# motor_driver.net
KiCad netlist of a schematic drawn in EAGLE
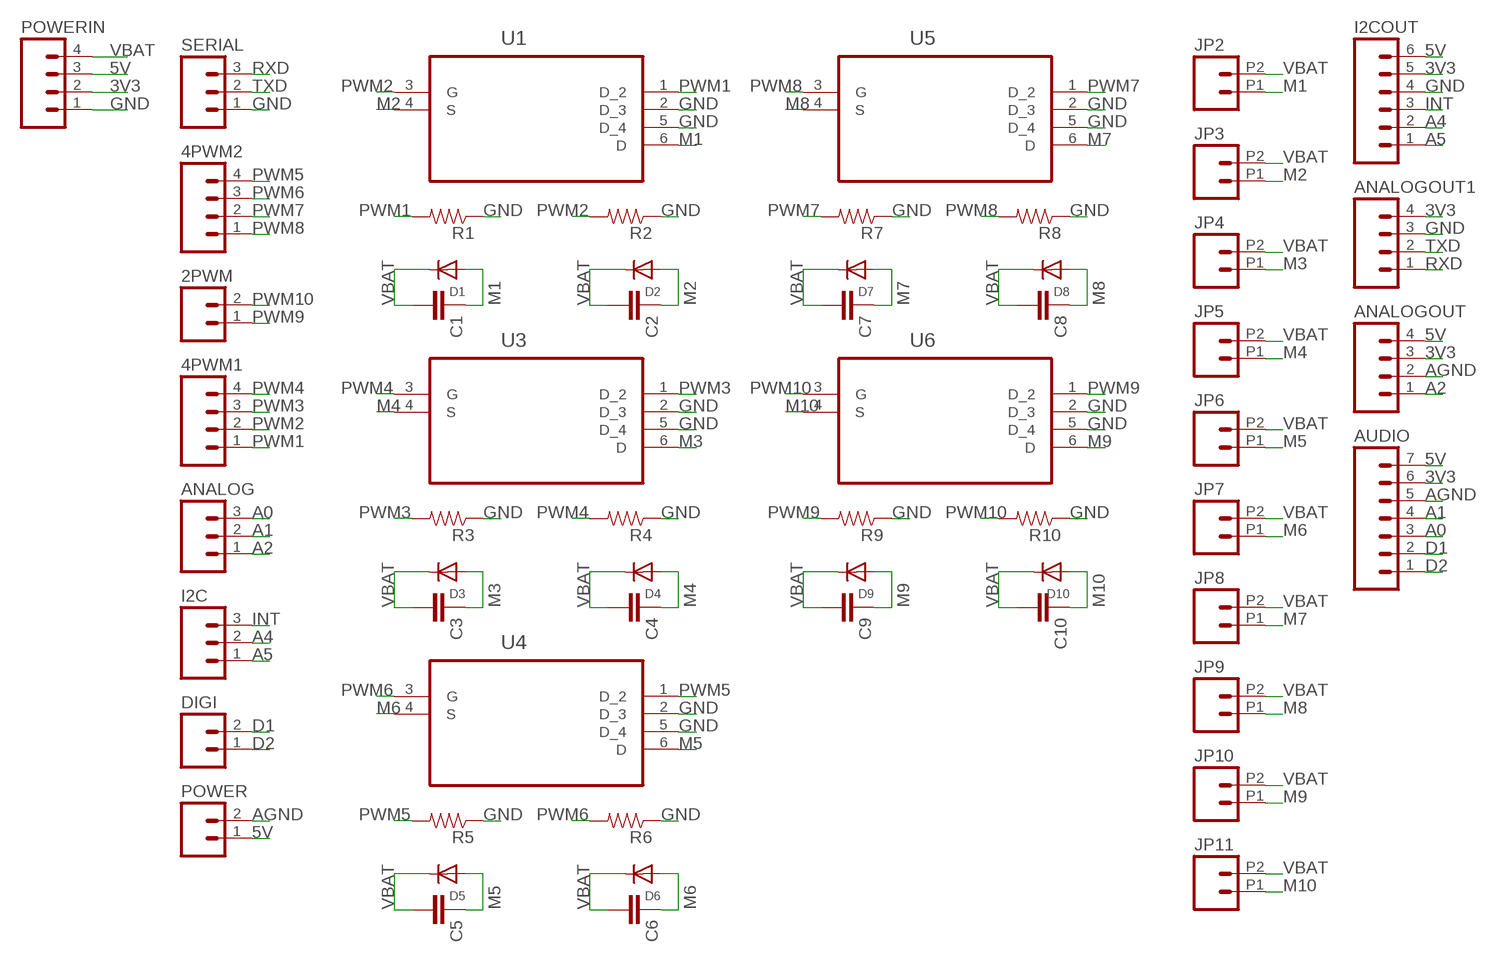
[diagram p0: schematic, sheet 1]

(export (version "E")
  (design (tool "Eeschema 10.0.6"))
  (components
    (comp (ref "2PWM")
      (value "M02PTH")
      (footprint "eagle-import:1X02")
      (libsource (lib "eagle-import") (part "M02PTH"))
    )
    (comp (ref "4PWM1")
      (value "M04PTH")
      (footprint "eagle-import:1X04")
      (libsource (lib "eagle-import") (part "M04PTH"))
    )
    (comp (ref "4PWM2")
      (value "M04PTH")
      (footprint "eagle-import:1X04")
      (libsource (lib "eagle-import") (part "M04PTH"))
    )
    (comp (ref "ANALOG")
      (value "M03PTH")
      (footprint "eagle-import:1X03")
      (libsource (lib "eagle-import") (part "M03PTH"))
    )
    (comp (ref "ANALOGOUT")
      (value "M04PTH")
      (footprint "eagle-import:1X04")
      (libsource (lib "eagle-import") (part "M04PTH"))
    )
    (comp (ref "ANALOGOUT1")
      (value "M04PTH")
      (footprint "eagle-import:1X04")
      (libsource (lib "eagle-import") (part "M04PTH"))
    )
    (comp (ref "AUDIO")
      (value "M07")
      (footprint "eagle-import:1X07")
      (libsource (lib "eagle-import") (part "M07"))
    )
    (comp (ref "C1")
      (value "CAP0603-CAP")
      (footprint "eagle-import:0603-CAP")
      (libsource (lib "eagle-import") (part "CAP0603-CAP"))
    )
    (comp (ref "C2")
      (value "CAP0603-CAP")
      (footprint "eagle-import:0603-CAP")
      (libsource (lib "eagle-import") (part "CAP0603-CAP"))
    )
    (comp (ref "C3")
      (value "CAP0603-CAP")
      (footprint "eagle-import:0603-CAP")
      (libsource (lib "eagle-import") (part "CAP0603-CAP"))
    )
    (comp (ref "C4")
      (value "CAP0603-CAP")
      (footprint "eagle-import:0603-CAP")
      (libsource (lib "eagle-import") (part "CAP0603-CAP"))
    )
    (comp (ref "C5")
      (value "CAP0603-CAP")
      (footprint "eagle-import:0603-CAP")
      (libsource (lib "eagle-import") (part "CAP0603-CAP"))
    )
    (comp (ref "C6")
      (value "CAP0603-CAP")
      (footprint "eagle-import:0603-CAP")
      (libsource (lib "eagle-import") (part "CAP0603-CAP"))
    )
    (comp (ref "C7")
      (value "CAP0603-CAP")
      (footprint "eagle-import:0603-CAP")
      (libsource (lib "eagle-import") (part "CAP0603-CAP"))
    )
    (comp (ref "C8")
      (value "CAP0603-CAP")
      (footprint "eagle-import:0603-CAP")
      (libsource (lib "eagle-import") (part "CAP0603-CAP"))
    )
    (comp (ref "C9")
      (value "CAP0603-CAP")
      (footprint "eagle-import:0603-CAP")
      (libsource (lib "eagle-import") (part "CAP0603-CAP"))
    )
    (comp (ref "C10")
      (value "CAP0603-CAP")
      (footprint "eagle-import:0603-CAP")
      (libsource (lib "eagle-import") (part "CAP0603-CAP"))
    )
    (comp (ref "D1")
      (value "DIODE_SOD-123FL")
      (footprint "eagle-import:SOD-123FL")
      (libsource (lib "eagle-import") (part "DIODE_SOD-123FL"))
    )
    (comp (ref "D2")
      (value "DIODE_SOD-123FL")
      (footprint "eagle-import:SOD-123FL")
      (libsource (lib "eagle-import") (part "DIODE_SOD-123FL"))
    )
    (comp (ref "D3")
      (value "DIODE_SOD-123FL")
      (footprint "eagle-import:SOD-123FL")
      (libsource (lib "eagle-import") (part "DIODE_SOD-123FL"))
    )
    (comp (ref "D4")
      (value "DIODE_SOD-123FL")
      (footprint "eagle-import:SOD-123FL")
      (libsource (lib "eagle-import") (part "DIODE_SOD-123FL"))
    )
    (comp (ref "D5")
      (value "DIODE_SOD-123FL")
      (footprint "eagle-import:SOD-123FL")
      (libsource (lib "eagle-import") (part "DIODE_SOD-123FL"))
    )
    (comp (ref "D6")
      (value "DIODE_SOD-123FL")
      (footprint "eagle-import:SOD-123FL")
      (libsource (lib "eagle-import") (part "DIODE_SOD-123FL"))
    )
    (comp (ref "D7")
      (value "DIODE_SOD-123FL")
      (footprint "eagle-import:SOD-123FL")
      (libsource (lib "eagle-import") (part "DIODE_SOD-123FL"))
    )
    (comp (ref "D8")
      (value "DIODE_SOD-123FL")
      (footprint "eagle-import:SOD-123FL")
      (libsource (lib "eagle-import") (part "DIODE_SOD-123FL"))
    )
    (comp (ref "D9")
      (value "DIODE_SOD-123FL")
      (footprint "eagle-import:SOD-123FL")
      (libsource (lib "eagle-import") (part "DIODE_SOD-123FL"))
    )
    (comp (ref "D10")
      (value "DIODE_SOD-123FL")
      (footprint "eagle-import:SOD-123FL")
      (libsource (lib "eagle-import") (part "DIODE_SOD-123FL"))
    )
    (comp (ref "DIGI")
      (value "M02PTH")
      (footprint "eagle-import:1X02")
      (libsource (lib "eagle-import") (part "M02PTH"))
    )
    (comp (ref "I2C")
      (value "M03PTH")
      (footprint "eagle-import:1X03")
      (libsource (lib "eagle-import") (part "M03PTH"))
    )
    (comp (ref "I2COUT")
      (value "M06NO_SILK")
      (footprint "eagle-import:1X06_NO_SILK")
      (libsource (lib "eagle-import") (part "M06NO_SILK"))
    )
    (comp (ref "JP2")
      (value "M022.54MM_SCREWTERM")
      (footprint "eagle-import:1X02_2.54_SCREWTERM")
      (libsource (lib "eagle-import") (part "M022.54MM_SCREWTERM"))
    )
    (comp (ref "JP3")
      (value "M022.54MM_SCREWTERM")
      (footprint "eagle-import:1X02_2.54_SCREWTERM")
      (libsource (lib "eagle-import") (part "M022.54MM_SCREWTERM"))
    )
    (comp (ref "JP4")
      (value "M022.54MM_SCREWTERM")
      (footprint "eagle-import:1X02_2.54_SCREWTERM")
      (libsource (lib "eagle-import") (part "M022.54MM_SCREWTERM"))
    )
    (comp (ref "JP5")
      (value "M022.54MM_SCREWTERM")
      (footprint "eagle-import:1X02_2.54_SCREWTERM")
      (libsource (lib "eagle-import") (part "M022.54MM_SCREWTERM"))
    )
    (comp (ref "JP6")
      (value "M022.54MM_SCREWTERM")
      (footprint "eagle-import:1X02_2.54_SCREWTERM")
      (libsource (lib "eagle-import") (part "M022.54MM_SCREWTERM"))
    )
    (comp (ref "JP7")
      (value "M022.54MM_SCREWTERM")
      (footprint "eagle-import:1X02_2.54_SCREWTERM")
      (libsource (lib "eagle-import") (part "M022.54MM_SCREWTERM"))
    )
    (comp (ref "JP8")
      (value "M022.54MM_SCREWTERM")
      (footprint "eagle-import:1X02_2.54_SCREWTERM")
      (libsource (lib "eagle-import") (part "M022.54MM_SCREWTERM"))
    )
    (comp (ref "JP9")
      (value "M022.54MM_SCREWTERM")
      (footprint "eagle-import:1X02_2.54_SCREWTERM")
      (libsource (lib "eagle-import") (part "M022.54MM_SCREWTERM"))
    )
    (comp (ref "JP10")
      (value "M022.54MM_SCREWTERM")
      (footprint "eagle-import:1X02_2.54_SCREWTERM")
      (libsource (lib "eagle-import") (part "M022.54MM_SCREWTERM"))
    )
    (comp (ref "JP11")
      (value "M022.54MM_SCREWTERM")
      (footprint "eagle-import:1X02_2.54_SCREWTERM")
      (libsource (lib "eagle-import") (part "M022.54MM_SCREWTERM"))
    )
    (comp (ref "POWER")
      (value "M02PTH")
      (footprint "eagle-import:1X02")
      (libsource (lib "eagle-import") (part "M02PTH"))
    )
    (comp (ref "POWERIN")
      (value "M04PTH")
      (footprint "eagle-import:1X04")
      (libsource (lib "eagle-import") (part "M04PTH"))
    )
    (comp (ref "R1")
      (value "RESISTOR0603")
      (footprint "eagle-import:0603-RES")
      (libsource (lib "eagle-import") (part "RESISTOR0603"))
    )
    (comp (ref "R2")
      (value "RESISTOR0603")
      (footprint "eagle-import:0603-RES")
      (libsource (lib "eagle-import") (part "RESISTOR0603"))
    )
    (comp (ref "R3")
      (value "RESISTOR0603")
      (footprint "eagle-import:0603-RES")
      (libsource (lib "eagle-import") (part "RESISTOR0603"))
    )
    (comp (ref "R4")
      (value "RESISTOR0603")
      (footprint "eagle-import:0603-RES")
      (libsource (lib "eagle-import") (part "RESISTOR0603"))
    )
    (comp (ref "R5")
      (value "RESISTOR0603")
      (footprint "eagle-import:0603-RES")
      (libsource (lib "eagle-import") (part "RESISTOR0603"))
    )
    (comp (ref "R6")
      (value "RESISTOR0603")
      (footprint "eagle-import:0603-RES")
      (libsource (lib "eagle-import") (part "RESISTOR0603"))
    )
    (comp (ref "R7")
      (value "RESISTOR0603")
      (footprint "eagle-import:0603-RES")
      (libsource (lib "eagle-import") (part "RESISTOR0603"))
    )
    (comp (ref "R8")
      (value "RESISTOR0603")
      (footprint "eagle-import:0603-RES")
      (libsource (lib "eagle-import") (part "RESISTOR0603"))
    )
    (comp (ref "R9")
      (value "RESISTOR0603")
      (footprint "eagle-import:0603-RES")
      (libsource (lib "eagle-import") (part "RESISTOR0603"))
    )
    (comp (ref "R10")
      (value "RESISTOR0603")
      (footprint "eagle-import:0603-RES")
      (libsource (lib "eagle-import") (part "RESISTOR0603"))
    )
    (comp (ref "SERIAL")
      (value "M03PTH")
      (footprint "eagle-import:1X03")
      (libsource (lib "eagle-import") (part "M03PTH"))
    )
    (comp (ref "U1")
      (value "SI3456DDV-T1-GE3")
      (footprint "eagle-import:SOT95P285X110-6N")
      (libsource (lib "eagle-import") (part "SI3456DDV-T1-GE3"))
    )
    (comp (ref "U3")
      (value "SI3456DDV-T1-GE3")
      (footprint "eagle-import:SOT95P285X110-6N")
      (libsource (lib "eagle-import") (part "SI3456DDV-T1-GE3"))
    )
    (comp (ref "U4")
      (value "SI3456DDV-T1-GE3")
      (footprint "eagle-import:SOT95P285X110-6N")
      (libsource (lib "eagle-import") (part "SI3456DDV-T1-GE3"))
    )
    (comp (ref "U5")
      (value "SI3456DDV-T1-GE3")
      (footprint "eagle-import:SOT95P285X110-6N")
      (libsource (lib "eagle-import") (part "SI3456DDV-T1-GE3"))
    )
    (comp (ref "U6")
      (value "SI3456DDV-T1-GE3")
      (footprint "eagle-import:SOT95P285X110-6N")
      (libsource (lib "eagle-import") (part "SI3456DDV-T1-GE3"))
    )
  )
  (nets
    (net (code "1") (name "/3V3") (class "Default")
      (node (ref "ANALOGOUT") (pin "3") (pinfunction "3_3") (pintype "passive"))
      (node (ref "ANALOGOUT1") (pin "4") (pinfunction "4_4") (pintype "passive"))
      (node (ref "AUDIO") (pin "6") (pinfunction "6_6") (pintype "passive"))
      (node (ref "I2COUT") (pin "5") (pinfunction "5_5") (pintype "passive"))
      (node (ref "POWERIN") (pin "2") (pinfunction "2_2") (pintype "passive"))
    )
    (net (code "2") (name "/5V") (class "Default")
      (node (ref "ANALOGOUT") (pin "4") (pinfunction "4_4") (pintype "passive"))
      (node (ref "AUDIO") (pin "7") (pinfunction "7_7") (pintype "passive"))
      (node (ref "I2COUT") (pin "6") (pinfunction "6_6") (pintype "passive"))
      (node (ref "POWER") (pin "1") (pinfunction "1_1") (pintype "passive"))
      (node (ref "POWERIN") (pin "3") (pinfunction "3_3") (pintype "passive"))
    )
    (net (code "3") (name "/A0") (class "Default")
      (node (ref "ANALOG") (pin "3") (pinfunction "3_3") (pintype "passive"))
      (node (ref "AUDIO") (pin "3") (pinfunction "3_3") (pintype "passive"))
    )
    (net (code "4") (name "/A1") (class "Default")
      (node (ref "ANALOG") (pin "2") (pinfunction "2_2") (pintype "passive"))
      (node (ref "AUDIO") (pin "4") (pinfunction "4_4") (pintype "passive"))
    )
    (net (code "5") (name "/A2") (class "Default")
      (node (ref "ANALOG") (pin "1") (pinfunction "1_1") (pintype "passive"))
      (node (ref "ANALOGOUT") (pin "1") (pinfunction "1_1") (pintype "passive"))
    )
    (net (code "6") (name "/A4") (class "Default")
      (node (ref "I2C") (pin "2") (pinfunction "2_2") (pintype "passive"))
      (node (ref "I2COUT") (pin "2") (pinfunction "2_2") (pintype "passive"))
    )
    (net (code "7") (name "/A5") (class "Default")
      (node (ref "I2C") (pin "1") (pinfunction "1_1") (pintype "passive"))
      (node (ref "I2COUT") (pin "1") (pinfunction "1_1") (pintype "passive"))
    )
    (net (code "8") (name "/AGND") (class "Default")
      (node (ref "ANALOGOUT") (pin "2") (pinfunction "2_2") (pintype "passive"))
      (node (ref "AUDIO") (pin "5") (pinfunction "5_5") (pintype "passive"))
      (node (ref "POWER") (pin "2") (pinfunction "2_2") (pintype "passive"))
    )
    (net (code "9") (name "/D1") (class "Default")
      (node (ref "AUDIO") (pin "2") (pinfunction "2_2") (pintype "passive"))
      (node (ref "DIGI") (pin "2") (pinfunction "2_2") (pintype "passive"))
    )
    (net (code "10") (name "/D2") (class "Default")
      (node (ref "AUDIO") (pin "1") (pinfunction "1_1") (pintype "passive"))
      (node (ref "DIGI") (pin "1") (pinfunction "1_1") (pintype "passive"))
    )
    (net (code "11") (name "/GND") (class "Default")
      (node (ref "ANALOGOUT1") (pin "3") (pinfunction "3_3") (pintype "passive"))
      (node (ref "I2COUT") (pin "4") (pinfunction "4_4") (pintype "passive"))
      (node (ref "POWERIN") (pin "1") (pinfunction "1_1") (pintype "passive"))
      (node (ref "R1") (pin "1") (pinfunction "1_1") (pintype "passive"))
      (node (ref "R10") (pin "1") (pinfunction "1_1") (pintype "passive"))
      (node (ref "R2") (pin "1") (pinfunction "1_1") (pintype "passive"))
      (node (ref "R3") (pin "1") (pinfunction "1_1") (pintype "passive"))
      (node (ref "R4") (pin "1") (pinfunction "1_1") (pintype "passive"))
      (node (ref "R5") (pin "1") (pinfunction "1_1") (pintype "passive"))
      (node (ref "R6") (pin "1") (pinfunction "1_1") (pintype "passive"))
      (node (ref "R7") (pin "1") (pinfunction "1_1") (pintype "passive"))
      (node (ref "R8") (pin "1") (pinfunction "1_1") (pintype "passive"))
      (node (ref "R9") (pin "1") (pinfunction "1_1") (pintype "passive"))
      (node (ref "SERIAL") (pin "1") (pinfunction "1_1") (pintype "passive"))
      (node (ref "U1") (pin "2") (pinfunction "D_3_2") (pintype "passive"))
      (node (ref "U1") (pin "5") (pinfunction "D_4_5") (pintype "passive"))
      (node (ref "U3") (pin "2") (pinfunction "D_3_2") (pintype "passive"))
      (node (ref "U3") (pin "5") (pinfunction "D_4_5") (pintype "passive"))
      (node (ref "U4") (pin "2") (pinfunction "D_3_2") (pintype "passive"))
      (node (ref "U4") (pin "5") (pinfunction "D_4_5") (pintype "passive"))
      (node (ref "U5") (pin "2") (pinfunction "D_3_2") (pintype "passive"))
      (node (ref "U5") (pin "5") (pinfunction "D_4_5") (pintype "passive"))
      (node (ref "U6") (pin "2") (pinfunction "D_3_2") (pintype "passive"))
      (node (ref "U6") (pin "5") (pinfunction "D_4_5") (pintype "passive"))
    )
    (net (code "12") (name "/INT") (class "Default")
      (node (ref "I2C") (pin "3") (pinfunction "3_3") (pintype "passive"))
      (node (ref "I2COUT") (pin "3") (pinfunction "3_3") (pintype "passive"))
    )
    (net (code "13") (name "/M1") (class "Default")
      (node (ref "C1") (pin "1") (pinfunction "1_1") (pintype "passive"))
      (node (ref "D1") (pin "A") (pinfunction "A_A") (pintype "passive"))
      (node (ref "JP2") (pin "P1") (pinfunction "1_P1") (pintype "passive"))
      (node (ref "U1") (pin "6") (pinfunction "D_6") (pintype "passive"))
    )
    (net (code "14") (name "/M2") (class "Default")
      (node (ref "C2") (pin "1") (pinfunction "1_1") (pintype "passive"))
      (node (ref "D2") (pin "A") (pinfunction "A_A") (pintype "passive"))
      (node (ref "JP3") (pin "P1") (pinfunction "1_P1") (pintype "passive"))
      (node (ref "U1") (pin "4") (pinfunction "S_4") (pintype "passive"))
    )
    (net (code "15") (name "/M3") (class "Default")
      (node (ref "C3") (pin "1") (pinfunction "1_1") (pintype "passive"))
      (node (ref "D3") (pin "A") (pinfunction "A_A") (pintype "passive"))
      (node (ref "JP4") (pin "P1") (pinfunction "1_P1") (pintype "passive"))
      (node (ref "U3") (pin "6") (pinfunction "D_6") (pintype "passive"))
    )
    (net (code "16") (name "/M4") (class "Default")
      (node (ref "C4") (pin "1") (pinfunction "1_1") (pintype "passive"))
      (node (ref "D4") (pin "A") (pinfunction "A_A") (pintype "passive"))
      (node (ref "JP5") (pin "P1") (pinfunction "1_P1") (pintype "passive"))
      (node (ref "U3") (pin "4") (pinfunction "S_4") (pintype "passive"))
    )
    (net (code "17") (name "/M5") (class "Default")
      (node (ref "C5") (pin "1") (pinfunction "1_1") (pintype "passive"))
      (node (ref "D5") (pin "A") (pinfunction "A_A") (pintype "passive"))
      (node (ref "JP6") (pin "P1") (pinfunction "1_P1") (pintype "passive"))
      (node (ref "U4") (pin "6") (pinfunction "D_6") (pintype "passive"))
    )
    (net (code "18") (name "/M6") (class "Default")
      (node (ref "C6") (pin "1") (pinfunction "1_1") (pintype "passive"))
      (node (ref "D6") (pin "A") (pinfunction "A_A") (pintype "passive"))
      (node (ref "JP7") (pin "P1") (pinfunction "1_P1") (pintype "passive"))
      (node (ref "U4") (pin "4") (pinfunction "S_4") (pintype "passive"))
    )
    (net (code "19") (name "/M7") (class "Default")
      (node (ref "C7") (pin "1") (pinfunction "1_1") (pintype "passive"))
      (node (ref "D7") (pin "A") (pinfunction "A_A") (pintype "passive"))
      (node (ref "JP8") (pin "P1") (pinfunction "1_P1") (pintype "passive"))
      (node (ref "U5") (pin "6") (pinfunction "D_6") (pintype "passive"))
    )
    (net (code "20") (name "/M8") (class "Default")
      (node (ref "C8") (pin "1") (pinfunction "1_1") (pintype "passive"))
      (node (ref "D8") (pin "A") (pinfunction "A_A") (pintype "passive"))
      (node (ref "JP9") (pin "P1") (pinfunction "1_P1") (pintype "passive"))
      (node (ref "U5") (pin "4") (pinfunction "S_4") (pintype "passive"))
    )
    (net (code "21") (name "/M9") (class "Default")
      (node (ref "C9") (pin "1") (pinfunction "1_1") (pintype "passive"))
      (node (ref "D9") (pin "A") (pinfunction "A_A") (pintype "passive"))
      (node (ref "JP10") (pin "P1") (pinfunction "1_P1") (pintype "passive"))
      (node (ref "U6") (pin "6") (pinfunction "D_6") (pintype "passive"))
    )
    (net (code "22") (name "/M10") (class "Default")
      (node (ref "C10") (pin "1") (pinfunction "1_1") (pintype "passive"))
      (node (ref "D10") (pin "A") (pinfunction "A_A") (pintype "passive"))
      (node (ref "JP11") (pin "P1") (pinfunction "1_P1") (pintype "passive"))
      (node (ref "U6") (pin "4") (pinfunction "S_4") (pintype "passive"))
    )
    (net (code "23") (name "/PWM1") (class "Default")
      (node (ref "4PWM1") (pin "1") (pinfunction "1_1") (pintype "passive"))
      (node (ref "R1") (pin "2") (pinfunction "2_2") (pintype "passive"))
      (node (ref "U1") (pin "1") (pinfunction "D_2_1") (pintype "passive"))
    )
    (net (code "24") (name "/PWM2") (class "Default")
      (node (ref "4PWM1") (pin "2") (pinfunction "2_2") (pintype "passive"))
      (node (ref "R2") (pin "2") (pinfunction "2_2") (pintype "passive"))
      (node (ref "U1") (pin "3") (pinfunction "G_3") (pintype "passive"))
    )
    (net (code "25") (name "/PWM3") (class "Default")
      (node (ref "4PWM1") (pin "3") (pinfunction "3_3") (pintype "passive"))
      (node (ref "R3") (pin "2") (pinfunction "2_2") (pintype "passive"))
      (node (ref "U3") (pin "1") (pinfunction "D_2_1") (pintype "passive"))
    )
    (net (code "26") (name "/PWM4") (class "Default")
      (node (ref "4PWM1") (pin "4") (pinfunction "4_4") (pintype "passive"))
      (node (ref "R4") (pin "2") (pinfunction "2_2") (pintype "passive"))
      (node (ref "U3") (pin "3") (pinfunction "G_3") (pintype "passive"))
    )
    (net (code "27") (name "/PWM5") (class "Default")
      (node (ref "4PWM2") (pin "4") (pinfunction "4_4") (pintype "passive"))
      (node (ref "R5") (pin "2") (pinfunction "2_2") (pintype "passive"))
      (node (ref "U4") (pin "1") (pinfunction "D_2_1") (pintype "passive"))
    )
    (net (code "28") (name "/PWM6") (class "Default")
      (node (ref "4PWM2") (pin "3") (pinfunction "3_3") (pintype "passive"))
      (node (ref "R6") (pin "2") (pinfunction "2_2") (pintype "passive"))
      (node (ref "U4") (pin "3") (pinfunction "G_3") (pintype "passive"))
    )
    (net (code "29") (name "/PWM7") (class "Default")
      (node (ref "4PWM2") (pin "2") (pinfunction "2_2") (pintype "passive"))
      (node (ref "R7") (pin "2") (pinfunction "2_2") (pintype "passive"))
      (node (ref "U5") (pin "1") (pinfunction "D_2_1") (pintype "passive"))
    )
    (net (code "30") (name "/PWM8") (class "Default")
      (node (ref "4PWM2") (pin "1") (pinfunction "1_1") (pintype "passive"))
      (node (ref "R8") (pin "2") (pinfunction "2_2") (pintype "passive"))
      (node (ref "U5") (pin "3") (pinfunction "G_3") (pintype "passive"))
    )
    (net (code "31") (name "/PWM9") (class "Default")
      (node (ref "2PWM") (pin "1") (pinfunction "1_1") (pintype "passive"))
      (node (ref "R9") (pin "2") (pinfunction "2_2") (pintype "passive"))
      (node (ref "U6") (pin "1") (pinfunction "D_2_1") (pintype "passive"))
    )
    (net (code "32") (name "/PWM10") (class "Default")
      (node (ref "2PWM") (pin "2") (pinfunction "2_2") (pintype "passive"))
      (node (ref "R10") (pin "2") (pinfunction "2_2") (pintype "passive"))
      (node (ref "U6") (pin "3") (pinfunction "G_3") (pintype "passive"))
    )
    (net (code "33") (name "/RXD") (class "Default")
      (node (ref "ANALOGOUT1") (pin "1") (pinfunction "1_1") (pintype "passive"))
      (node (ref "SERIAL") (pin "3") (pinfunction "3_3") (pintype "passive"))
    )
    (net (code "34") (name "/TXD") (class "Default")
      (node (ref "ANALOGOUT1") (pin "2") (pinfunction "2_2") (pintype "passive"))
      (node (ref "SERIAL") (pin "2") (pinfunction "2_2") (pintype "passive"))
    )
    (net (code "35") (name "/VBAT") (class "Default")
      (node (ref "C1") (pin "2") (pinfunction "2_2") (pintype "passive"))
      (node (ref "C10") (pin "2") (pinfunction "2_2") (pintype "passive"))
      (node (ref "C2") (pin "2") (pinfunction "2_2") (pintype "passive"))
      (node (ref "C3") (pin "2") (pinfunction "2_2") (pintype "passive"))
      (node (ref "C4") (pin "2") (pinfunction "2_2") (pintype "passive"))
      (node (ref "C5") (pin "2") (pinfunction "2_2") (pintype "passive"))
      (node (ref "C6") (pin "2") (pinfunction "2_2") (pintype "passive"))
      (node (ref "C7") (pin "2") (pinfunction "2_2") (pintype "passive"))
      (node (ref "C8") (pin "2") (pinfunction "2_2") (pintype "passive"))
      (node (ref "C9") (pin "2") (pinfunction "2_2") (pintype "passive"))
      (node (ref "D1") (pin "C") (pinfunction "C_C") (pintype "passive"))
      (node (ref "D10") (pin "C") (pinfunction "C_C") (pintype "passive"))
      (node (ref "D2") (pin "C") (pinfunction "C_C") (pintype "passive"))
      (node (ref "D3") (pin "C") (pinfunction "C_C") (pintype "passive"))
      (node (ref "D4") (pin "C") (pinfunction "C_C") (pintype "passive"))
      (node (ref "D5") (pin "C") (pinfunction "C_C") (pintype "passive"))
      (node (ref "D6") (pin "C") (pinfunction "C_C") (pintype "passive"))
      (node (ref "D7") (pin "C") (pinfunction "C_C") (pintype "passive"))
      (node (ref "D8") (pin "C") (pinfunction "C_C") (pintype "passive"))
      (node (ref "D9") (pin "C") (pinfunction "C_C") (pintype "passive"))
      (node (ref "JP10") (pin "P2") (pinfunction "2_P2") (pintype "passive"))
      (node (ref "JP11") (pin "P2") (pinfunction "2_P2") (pintype "passive"))
      (node (ref "JP2") (pin "P2") (pinfunction "2_P2") (pintype "passive"))
      (node (ref "JP3") (pin "P2") (pinfunction "2_P2") (pintype "passive"))
      (node (ref "JP4") (pin "P2") (pinfunction "2_P2") (pintype "passive"))
      (node (ref "JP5") (pin "P2") (pinfunction "2_P2") (pintype "passive"))
      (node (ref "JP6") (pin "P2") (pinfunction "2_P2") (pintype "passive"))
      (node (ref "JP7") (pin "P2") (pinfunction "2_P2") (pintype "passive"))
      (node (ref "JP8") (pin "P2") (pinfunction "2_P2") (pintype "passive"))
      (node (ref "JP9") (pin "P2") (pinfunction "2_P2") (pintype "passive"))
      (node (ref "POWERIN") (pin "4") (pinfunction "4_4") (pintype "passive"))
    )
  )
)
